# Temperature_V_1_0.net
KiCad netlist of a schematic drawn in EAGLE
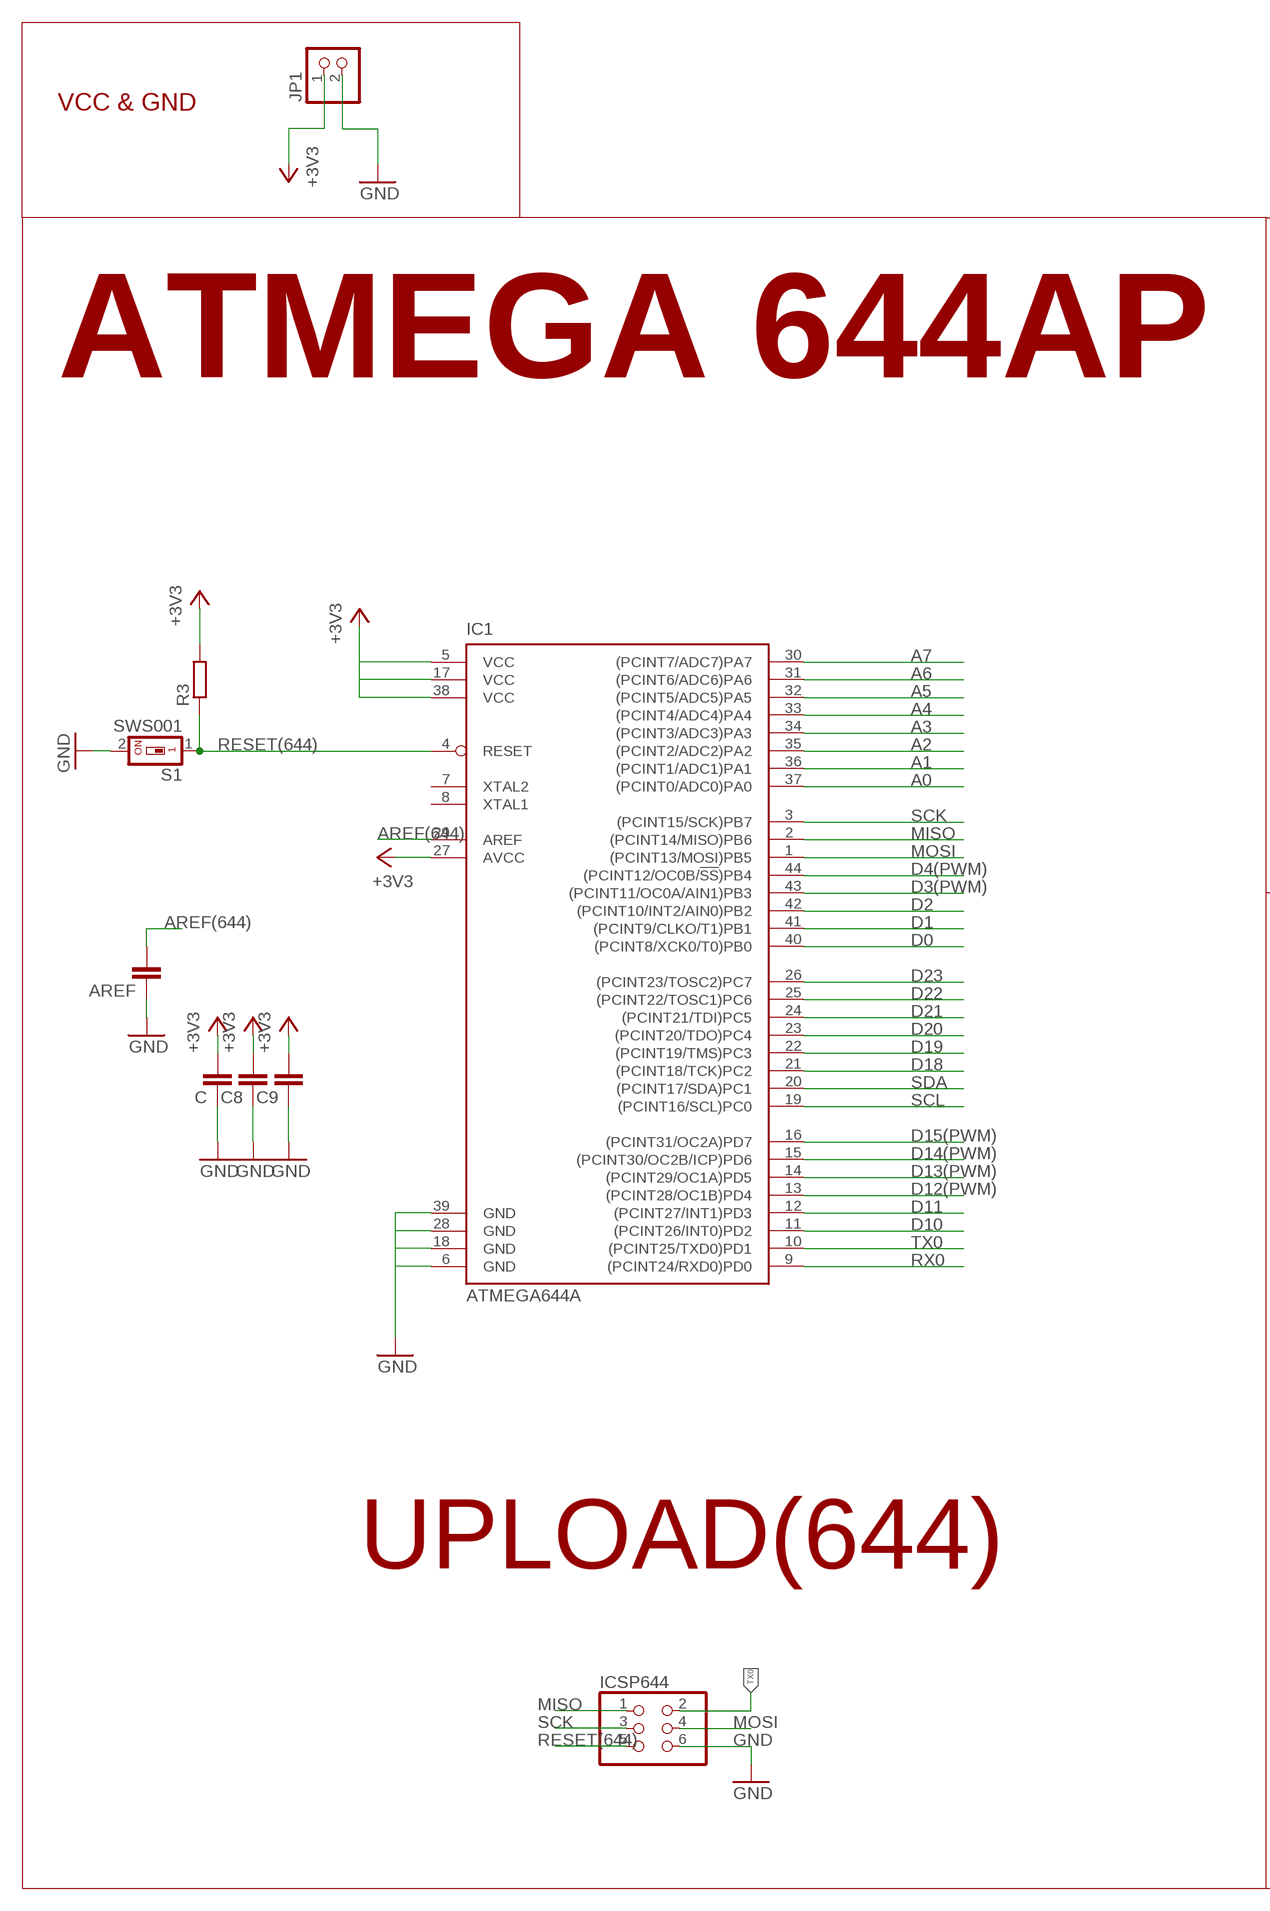
[diagram p0: schematic, sheet 1, part 1 of 2]
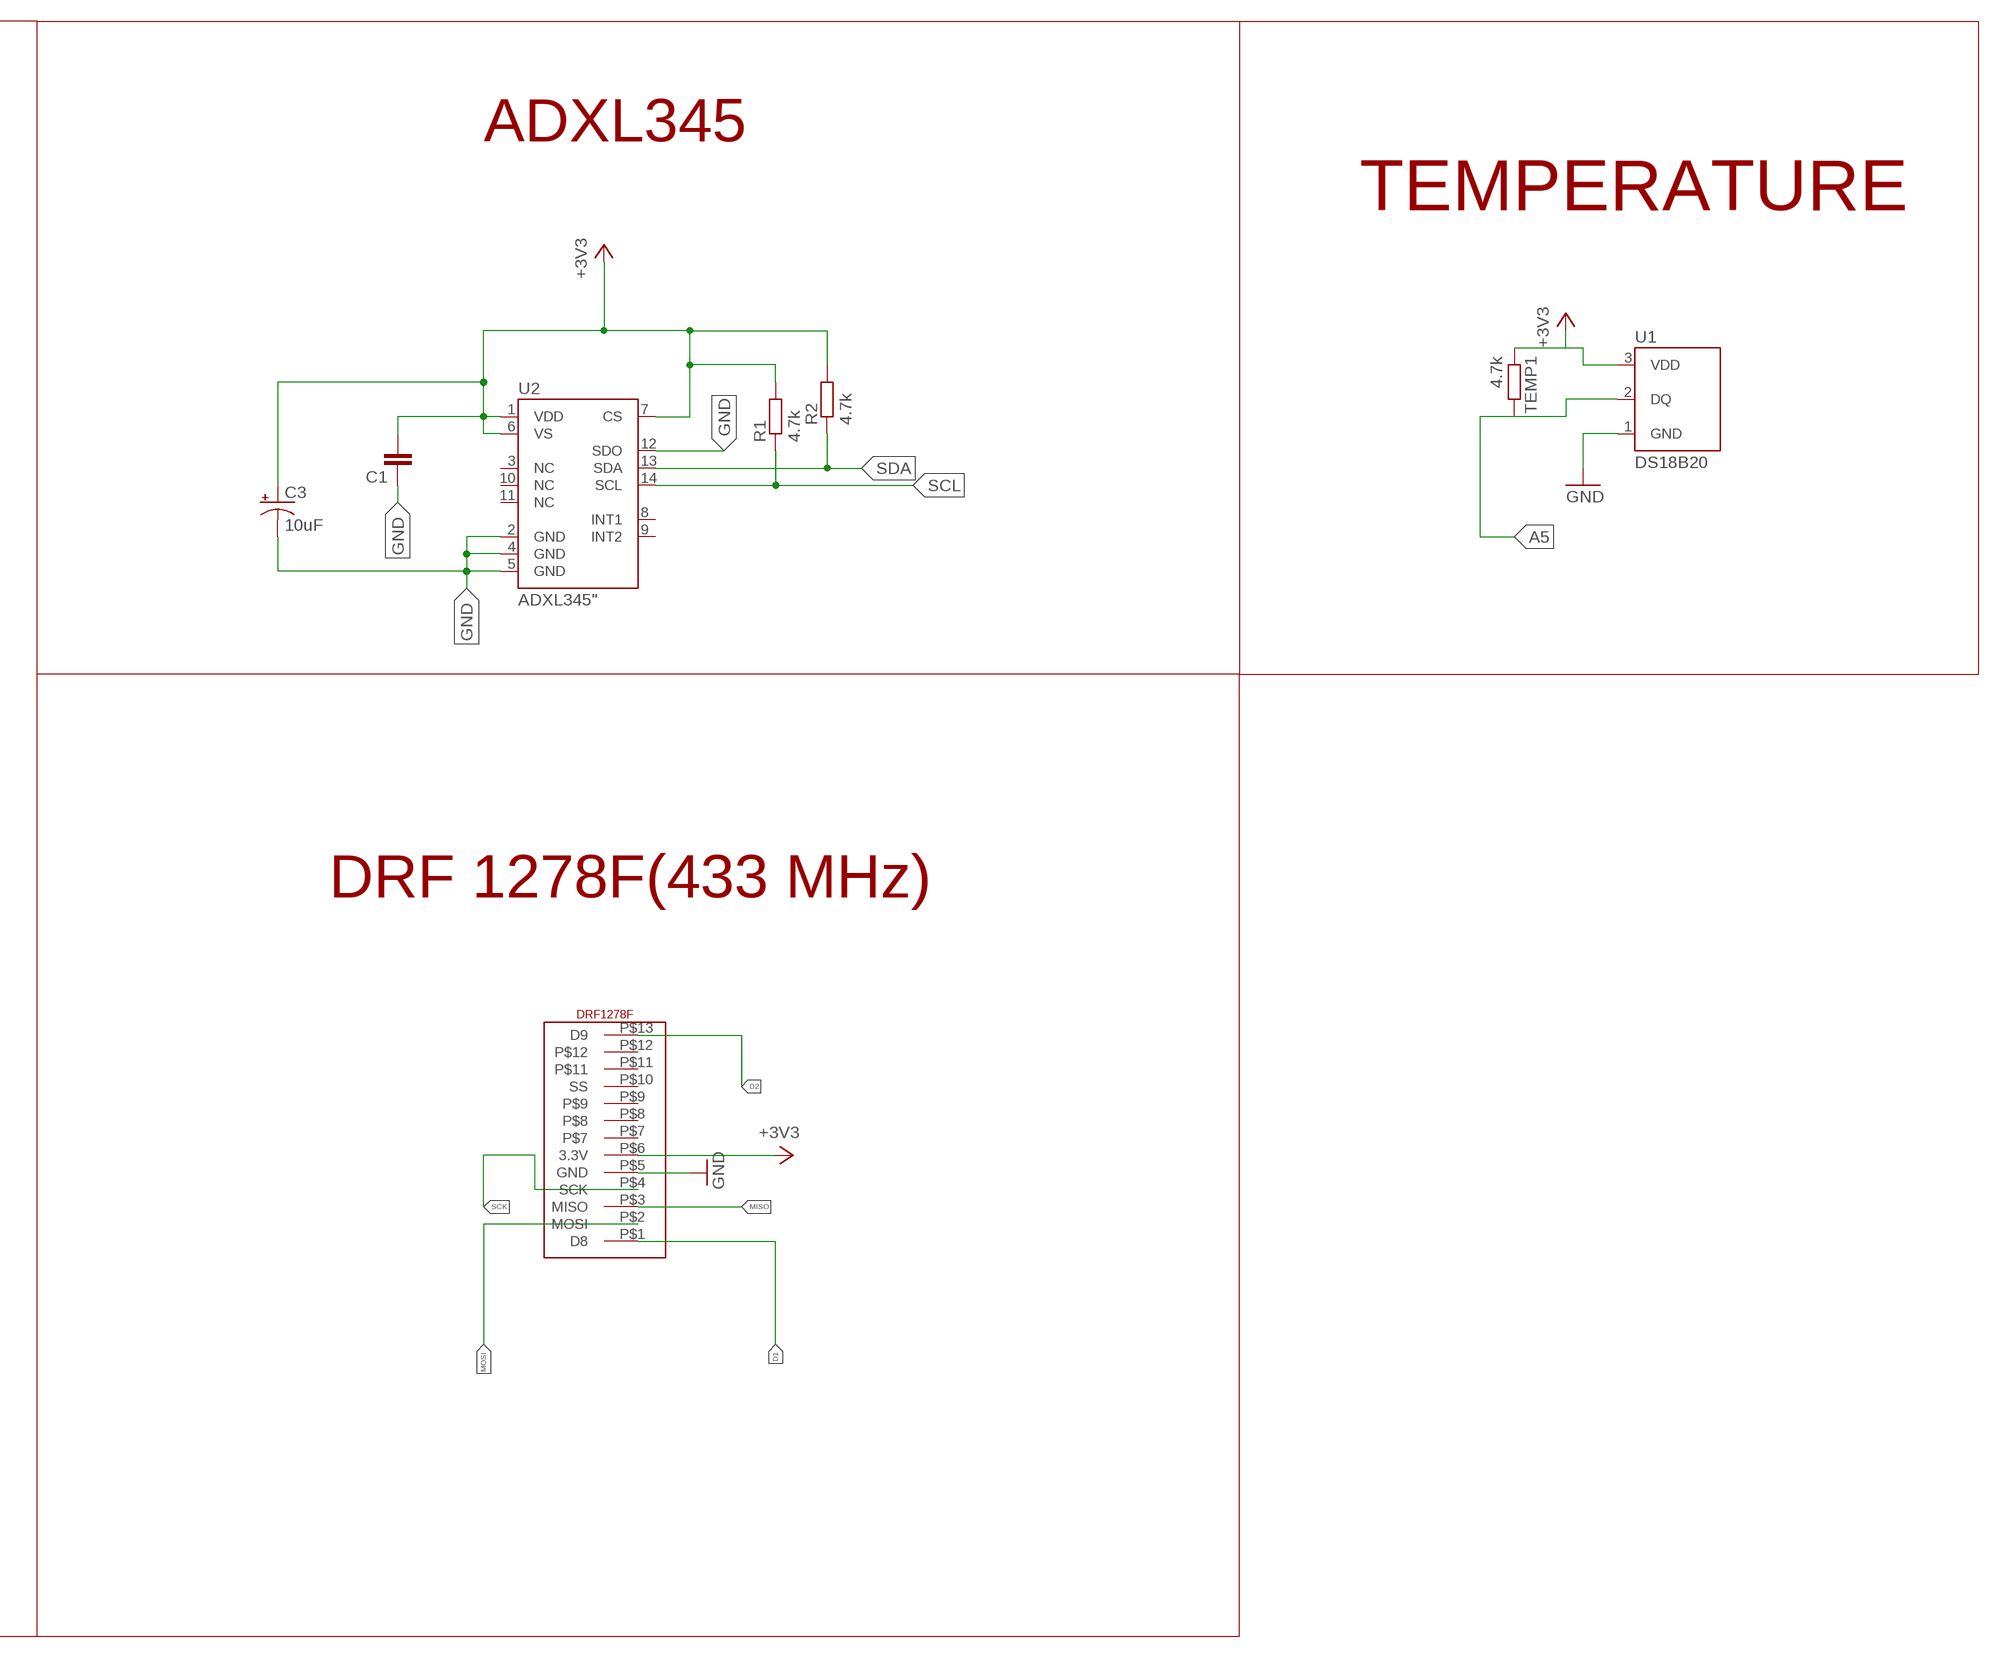
[diagram p1: schematic, sheet 1, part 2 of 2]

(export (version "E")
  (design (tool "Eeschema 10.0.6"))
  (components
    (comp (ref "AREF")
      (value "100nF")
      (footprint "eagle-import:C0805")
      (libsource (lib "eagle-import") (part "C-EUC0805"))
    )
    (comp (ref "C")
      (value "22 uF")
      (footprint "eagle-import:C0805")
      (libsource (lib "eagle-import") (part "C-EUC0805"))
    )
    (comp (ref "C1")
      (value "0.1uF")
      (footprint "eagle-import:C0805")
      (libsource (lib "eagle-import") (part "C-EUC0805"))
    )
    (comp (ref "C3")
      (value "10uF")
      (footprint "eagle-import:EIA3216")
      (libsource (lib "eagle-import") (part "CAP_POL1206"))
    )
    (comp (ref "C8")
      (value "100nF")
      (footprint "eagle-import:C0805")
      (libsource (lib "eagle-import") (part "C-EUC0805"))
    )
    (comp (ref "C9")
      (value "100nF")
      (footprint "eagle-import:C0805")
      (libsource (lib "eagle-import") (part "C-EUC0805"))
    )
    (comp (ref "IC1")
      (value "ATMEGA644A")
      (footprint "eagle-import:TQFP44")
      (fields (field (name "MPN") "ATMEGA644PV-10AU"))
      (libsource (lib "eagle-import") (part "ATMEGA644A"))
    )
    (comp (ref "ICSP644")
      (value "PINHD-2X3")
      (footprint "eagle-import:2X03")
      (libsource (lib "eagle-import") (part "PINHD-2X3"))
    )
    (comp (ref "JP1")
      (value "PINHD-1X2")
      (footprint "eagle-import:1X02")
      (libsource (lib "eagle-import") (part "PINHD-1X2"))
    )
    (comp (ref "R1")
      (value "4.7k")
      (footprint "eagle-import:R0805")
      (libsource (lib "eagle-import") (part "R-EU_R0805"))
    )
    (comp (ref "R2")
      (value "4.7k")
      (footprint "eagle-import:R0805")
      (libsource (lib "eagle-import") (part "R-EU_R0805"))
    )
    (comp (ref "R3")
      (value "R-EU_R0805")
      (footprint "eagle-import:R0805")
      (libsource (lib "eagle-import") (part "R-EU_R0805"))
    )
    (comp (ref "S1")
      (value "SWS001")
      (footprint "eagle-import:SMS-001")
      (libsource (lib "eagle-import") (part "SWS001"))
    )
    (comp (ref "TEMP1")
      (value "4.7k")
      (footprint "eagle-import:R0805")
      (libsource (lib "eagle-import") (part "R-EU_R0805"))
    )
    (comp (ref "U$1")
      (value "DRF1278F")
      (footprint "eagle-import:DIP13")
      (libsource (lib "eagle-import") (part "DRF1278F"))
    )
    (comp (ref "U1")
      (value "DS18B20")
      (footprint "eagle-import:TO-92-AMMO")
      (libsource (lib "eagle-import") (part "DS18B20"))
    )
    (comp (ref "U2")
      (value "ADXL345\"")
      (footprint "eagle-import:ADXL3451_1")
      (libsource (lib "eagle-import") (part "ADXL345{dblquote}"))
    )
  )
  (nets
    (net (code "1") (name "+3V3") (class "Default")
      (node (ref "C") (pin "2") (pinfunction "2_2") (pintype "passive"))
      (node (ref "C1") (pin "2") (pinfunction "2_2") (pintype "passive"))
      (node (ref "C3") (pin "A") (pinfunction "+_A") (pintype "passive"))
      (node (ref "C8") (pin "2") (pinfunction "2_2") (pintype "passive"))
      (node (ref "C9") (pin "2") (pinfunction "2_2") (pintype "passive"))
      (node (ref "IC1") (pin "17") (pinfunction "VCC_17") (pintype "power_in"))
      (node (ref "IC1") (pin "27") (pinfunction "AVCC_27") (pintype "power_in"))
      (node (ref "IC1") (pin "38") (pinfunction "VCC_38") (pintype "power_in"))
      (node (ref "IC1") (pin "5") (pinfunction "VCC_5") (pintype "power_in"))
      (node (ref "JP1") (pin "1") (pinfunction "1_1") (pintype "passive"))
      (node (ref "R1") (pin "2") (pinfunction "2_2") (pintype "passive"))
      (node (ref "R2") (pin "2") (pinfunction "2_2") (pintype "passive"))
      (node (ref "R3") (pin "2") (pinfunction "2_2") (pintype "passive"))
      (node (ref "TEMP1") (pin "1") (pinfunction "1_1") (pintype "passive"))
      (node (ref "U$1") (pin "P$6") (pinfunction "3.3V_P$6") (pintype "bidirectional"))
      (node (ref "U1") (pin "3") (pinfunction "VDD_3") (pintype "power_in"))
      (node (ref "U2") (pin "1") (pinfunction "VDD_1") (pintype "bidirectional"))
      (node (ref "U2") (pin "6") (pinfunction "VS_6") (pintype "bidirectional"))
      (node (ref "U2") (pin "7") (pinfunction "CS_7") (pintype "bidirectional"))
    )
    (net (code "2") (name "/A0") (class "Default")
      (node (ref "IC1") (pin "37") (pinfunction "(PCINT0/ADC0)PA0_37") (pintype "bidirectional"))
    )
    (net (code "3") (name "/A1") (class "Default")
      (node (ref "IC1") (pin "36") (pinfunction "(PCINT1/ADC1)PA1_36") (pintype "bidirectional"))
    )
    (net (code "4") (name "/A2") (class "Default")
      (node (ref "IC1") (pin "35") (pinfunction "(PCINT2/ADC2)PA2_35") (pintype "bidirectional"))
    )
    (net (code "5") (name "/A3") (class "Default")
      (node (ref "IC1") (pin "34") (pinfunction "(PCINT3/ADC3)PA3_34") (pintype "bidirectional"))
    )
    (net (code "6") (name "/A4") (class "Default")
      (node (ref "IC1") (pin "33") (pinfunction "(PCINT4/ADC4)PA4_33") (pintype "bidirectional"))
    )
    (net (code "7") (name "/A6") (class "Default")
      (node (ref "IC1") (pin "31") (pinfunction "(PCINT6/ADC6)PA6_31") (pintype "bidirectional"))
    )
    (net (code "8") (name "/A7") (class "Default")
      (node (ref "IC1") (pin "30") (pinfunction "(PCINT7/ADC7)PA7_30") (pintype "bidirectional"))
    )
    (net (code "9") (name "/AREF(644)") (class "Default")
      (node (ref "AREF") (pin "2") (pinfunction "2_2") (pintype "passive"))
      (node (ref "IC1") (pin "29") (pinfunction "AREF_29") (pintype "passive"))
    )
    (net (code "10") (name "/D0") (class "Default")
      (node (ref "IC1") (pin "40") (pinfunction "(PCINT8/XCK0/T0)PB0_40") (pintype "bidirectional"))
    )
    (net (code "11") (name "/D3(PWM)") (class "Default")
      (node (ref "IC1") (pin "43") (pinfunction "(PCINT11/OC0A/AIN1)PB3_43") (pintype "bidirectional"))
    )
    (net (code "12") (name "/D4(PWM)") (class "Default")
      (node (ref "IC1") (pin "44") (pinfunction "(PCINT12/OC0B/~{SS})PB4_44") (pintype "bidirectional"))
    )
    (net (code "13") (name "/D10") (class "Default")
      (node (ref "IC1") (pin "11") (pinfunction "(PCINT26/INT0)PD2_11") (pintype "bidirectional"))
    )
    (net (code "14") (name "/D11") (class "Default")
      (node (ref "IC1") (pin "12") (pinfunction "(PCINT27/INT1)PD3_12") (pintype "bidirectional"))
    )
    (net (code "15") (name "/D12(PWM)") (class "Default")
      (node (ref "IC1") (pin "13") (pinfunction "(PCINT28/OC1B)PD4_13") (pintype "bidirectional"))
    )
    (net (code "16") (name "/D13(PWM)") (class "Default")
      (node (ref "IC1") (pin "14") (pinfunction "(PCINT29/OC1A)PD5_14") (pintype "bidirectional"))
    )
    (net (code "17") (name "/D14(PWM)") (class "Default")
      (node (ref "IC1") (pin "15") (pinfunction "(PCINT30/OC2B/ICP)PD6_15") (pintype "bidirectional"))
    )
    (net (code "18") (name "/D15(PWM)") (class "Default")
      (node (ref "IC1") (pin "16") (pinfunction "(PCINT31/OC2A)PD7_16") (pintype "bidirectional"))
    )
    (net (code "19") (name "/D18") (class "Default")
      (node (ref "IC1") (pin "21") (pinfunction "(PCINT18/TCK)PC2_21") (pintype "output"))
    )
    (net (code "20") (name "/D19") (class "Default")
      (node (ref "IC1") (pin "22") (pinfunction "(PCINT19/TMS)PC3_22") (pintype "output"))
    )
    (net (code "21") (name "/D20") (class "Default")
      (node (ref "IC1") (pin "23") (pinfunction "(PCINT20/TDO)PC4_23") (pintype "output"))
    )
    (net (code "22") (name "/D21") (class "Default")
      (node (ref "IC1") (pin "24") (pinfunction "(PCINT21/TDI)PC5_24") (pintype "output"))
    )
    (net (code "23") (name "/D22") (class "Default")
      (node (ref "IC1") (pin "25") (pinfunction "(PCINT22/TOSC1)PC6_25") (pintype "output"))
    )
    (net (code "24") (name "/D23") (class "Default")
      (node (ref "IC1") (pin "26") (pinfunction "(PCINT23/TOSC2)PC7_26") (pintype "output"))
    )
    (net (code "25") (name "/RESET(644)") (class "Default")
      (node (ref "IC1") (pin "4") (pinfunction "RESET_4") (pintype "input"))
      (node (ref "ICSP644") (pin "5") (pinfunction "5_5") (pintype "passive"))
      (node (ref "R3") (pin "1") (pinfunction "1_1") (pintype "passive"))
      (node (ref "S1") (pin "1") (pinfunction "1_1") (pintype "passive"))
    )
    (net (code "26") (name "/RX0") (class "Default")
      (node (ref "IC1") (pin "9") (pinfunction "(PCINT24/RXD0)PD0_9") (pintype "bidirectional"))
    )
    (net (code "27") (name "A5") (class "Default")
      (node (ref "IC1") (pin "32") (pinfunction "(PCINT5/ADC5)PA5_32") (pintype "bidirectional"))
      (node (ref "TEMP1") (pin "2") (pinfunction "2_2") (pintype "passive"))
      (node (ref "U1") (pin "2") (pinfunction "DQ_2") (pintype "bidirectional"))
    )
    (net (code "28") (name "D1") (class "Default")
      (node (ref "IC1") (pin "41") (pinfunction "(PCINT9/CLKO/T1)PB1_41") (pintype "bidirectional"))
      (node (ref "U$1") (pin "P$1") (pinfunction "D8_P$1") (pintype "bidirectional"))
    )
    (net (code "29") (name "D2") (class "Default")
      (node (ref "IC1") (pin "42") (pinfunction "(PCINT10/INT2/AIN0)PB2_42") (pintype "bidirectional"))
      (node (ref "U$1") (pin "P$13") (pinfunction "D9_P$13") (pintype "bidirectional"))
    )
    (net (code "30") (name "GND") (class "Default")
      (node (ref "AREF") (pin "1") (pinfunction "1_1") (pintype "passive"))
      (node (ref "C") (pin "1") (pinfunction "1_1") (pintype "passive"))
      (node (ref "C1") (pin "1") (pinfunction "1_1") (pintype "passive"))
      (node (ref "C3") (pin "C") (pinfunction "-_C") (pintype "passive"))
      (node (ref "C8") (pin "1") (pinfunction "1_1") (pintype "passive"))
      (node (ref "C9") (pin "1") (pinfunction "1_1") (pintype "passive"))
      (node (ref "IC1") (pin "18") (pinfunction "GND_18") (pintype "power_in"))
      (node (ref "IC1") (pin "28") (pinfunction "GND_28") (pintype "power_in"))
      (node (ref "IC1") (pin "39") (pinfunction "GND_39") (pintype "power_in"))
      (node (ref "IC1") (pin "6") (pinfunction "GND_6") (pintype "power_in"))
      (node (ref "ICSP644") (pin "6") (pinfunction "6_6") (pintype "passive"))
      (node (ref "JP1") (pin "2") (pinfunction "2_2") (pintype "passive"))
      (node (ref "S1") (pin "2") (pinfunction "2_2") (pintype "passive"))
      (node (ref "U$1") (pin "P$5") (pinfunction "GND_P$5") (pintype "bidirectional"))
      (node (ref "U1") (pin "1") (pinfunction "GND_1") (pintype "power_in"))
      (node (ref "U2") (pin "12") (pinfunction "SDO_12") (pintype "bidirectional"))
      (node (ref "U2") (pin "2") (pinfunction "GND_2") (pintype "bidirectional"))
      (node (ref "U2") (pin "4") (pinfunction "GND_4") (pintype "bidirectional"))
      (node (ref "U2") (pin "5") (pinfunction "GND_5") (pintype "bidirectional"))
    )
    (net (code "31") (name "MISO") (class "Default")
      (node (ref "IC1") (pin "2") (pinfunction "(PCINT14/MISO)PB6_2") (pintype "bidirectional"))
      (node (ref "ICSP644") (pin "1") (pinfunction "1_1") (pintype "passive"))
      (node (ref "U$1") (pin "P$3") (pinfunction "MISO_P$3") (pintype "bidirectional"))
    )
    (net (code "32") (name "MOSI") (class "Default")
      (node (ref "IC1") (pin "1") (pinfunction "(PCINT13/MOSI)PB5_1") (pintype "bidirectional"))
      (node (ref "ICSP644") (pin "4") (pinfunction "4_4") (pintype "passive"))
      (node (ref "U$1") (pin "P$2") (pinfunction "MOSI_P$2") (pintype "bidirectional"))
    )
    (net (code "33") (name "SCK") (class "Default")
      (node (ref "IC1") (pin "3") (pinfunction "(PCINT15/SCK)PB7_3") (pintype "bidirectional"))
      (node (ref "ICSP644") (pin "3") (pinfunction "3_3") (pintype "passive"))
      (node (ref "U$1") (pin "P$4") (pinfunction "SCK_P$4") (pintype "bidirectional"))
    )
    (net (code "34") (name "SCL") (class "Default")
      (node (ref "IC1") (pin "19") (pinfunction "(PCINT16/SCL)PC0_19") (pintype "output"))
      (node (ref "R1") (pin "1") (pinfunction "1_1") (pintype "passive"))
      (node (ref "U2") (pin "14") (pinfunction "SCL_14") (pintype "bidirectional"))
    )
    (net (code "35") (name "SDA") (class "Default")
      (node (ref "IC1") (pin "20") (pinfunction "(PCINT17/SDA)PC1_20") (pintype "output"))
      (node (ref "R2") (pin "1") (pinfunction "1_1") (pintype "passive"))
      (node (ref "U2") (pin "13") (pinfunction "SDA_13") (pintype "bidirectional"))
    )
    (net (code "36") (name "TX0") (class "Default")
      (node (ref "IC1") (pin "10") (pinfunction "(PCINT25/TXD0)PD1_10") (pintype "bidirectional"))
      (node (ref "ICSP644") (pin "2") (pinfunction "2_2") (pintype "passive"))
    )
    (net (code "37") (name "unconnected-(IC1-XTAL1-Pad8)") (class "Default")
      (node (ref "IC1") (pin "8") (pinfunction "XTAL1_8") (pintype "bidirectional"))
    )
    (net (code "38") (name "unconnected-(IC1-XTAL2-Pad7)") (class "Default")
      (node (ref "IC1") (pin "7") (pinfunction "XTAL2_7") (pintype "bidirectional"))
    )
    (net (code "39") (name "unconnected-(U$1-PadP$7)") (class "Default")
      (node (ref "U$1") (pin "P$7") (pinfunction "P$7_P$7") (pintype "bidirectional"))
    )
    (net (code "40") (name "unconnected-(U$1-PadP$8)") (class "Default")
      (node (ref "U$1") (pin "P$8") (pinfunction "P$8_P$8") (pintype "bidirectional"))
    )
    (net (code "41") (name "unconnected-(U$1-PadP$9)") (class "Default")
      (node (ref "U$1") (pin "P$9") (pinfunction "P$9_P$9") (pintype "bidirectional"))
    )
    (net (code "42") (name "unconnected-(U$1-PadP$11)") (class "Default")
      (node (ref "U$1") (pin "P$11") (pinfunction "P$11_P$11") (pintype "bidirectional"))
    )
    (net (code "43") (name "unconnected-(U$1-PadP$12)") (class "Default")
      (node (ref "U$1") (pin "P$12") (pinfunction "P$12_P$12") (pintype "bidirectional"))
    )
    (net (code "44") (name "unconnected-(U$1-SS-PadP$10)") (class "Default")
      (node (ref "U$1") (pin "P$10") (pinfunction "SS_P$10") (pintype "bidirectional"))
    )
    (net (code "45") (name "unconnected-(U2-INT1-Pad8)") (class "Default")
      (node (ref "U2") (pin "8") (pinfunction "INT1_8") (pintype "bidirectional"))
    )
    (net (code "46") (name "unconnected-(U2-INT2-Pad9)") (class "Default")
      (node (ref "U2") (pin "9") (pinfunction "INT2_9") (pintype "bidirectional"))
    )
    (net (code "47") (name "unconnected-(U2-NC-Pad3)") (class "Default")
      (node (ref "U2") (pin "3") (pinfunction "NC_3") (pintype "bidirectional"))
    )
    (net (code "48") (name "unconnected-(U2-NC-Pad10)") (class "Default")
      (node (ref "U2") (pin "10") (pinfunction "NC_10") (pintype "bidirectional"))
    )
    (net (code "49") (name "unconnected-(U2-NC-Pad11)") (class "Default")
      (node (ref "U2") (pin "11") (pinfunction "NC_11") (pintype "bidirectional"))
    )
  )
)
